# grbl_shield_hector.net
KiCad netlist of a schematic drawn in EAGLE
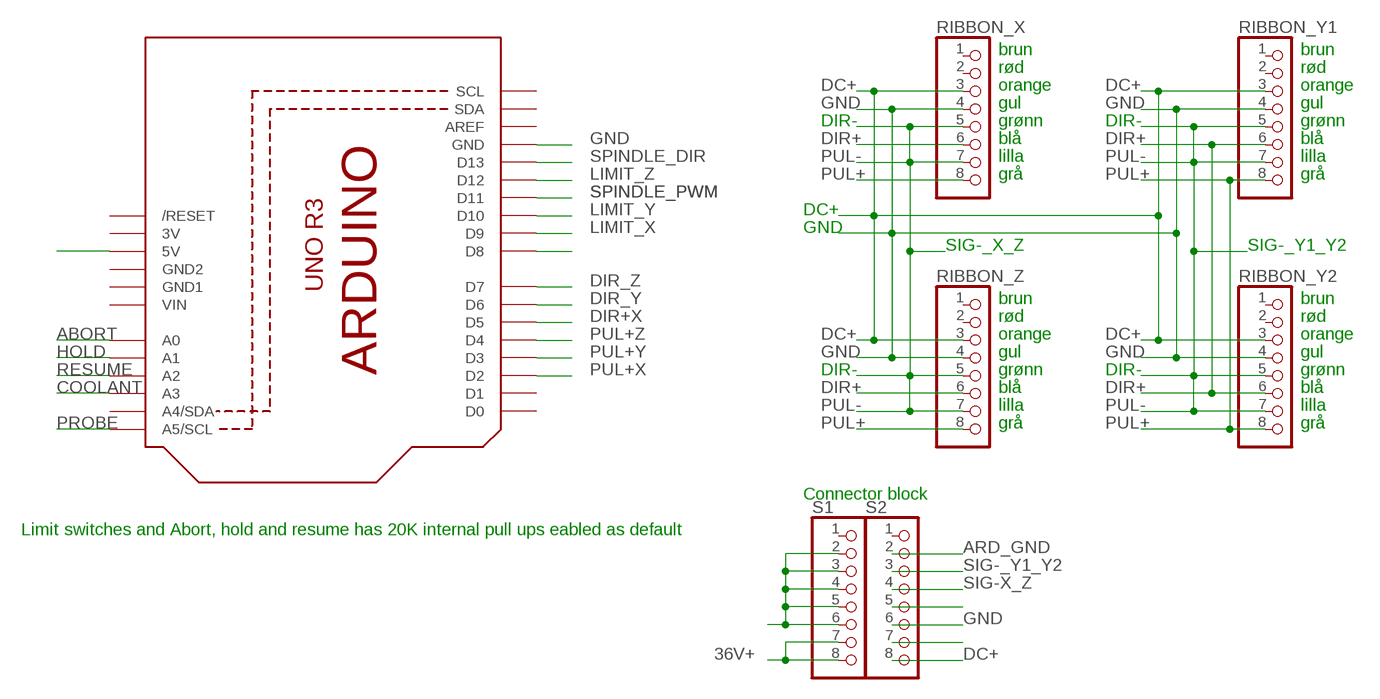
[diagram p0: schematic, sheet 1]

(export (version "E")
  (design (tool "Eeschema 10.0.6"))
  (components
    (comp (ref "Q1")
      (value "ARDUINOR3-NOIOREF-NOTEXT")
      (footprint "eagle-import:ARDUINOR3-NOTEXT-NOIOREF")
      (libsource (lib "eagle-import") (part "ARDUINOR3-NOIOREF-NOTEXT"))
    )
    (comp (ref "RIBBON_X")
      (value "PINHD-1X8")
      (footprint "eagle-import:1X08")
      (libsource (lib "eagle-import") (part "PINHD-1X8"))
    )
    (comp (ref "RIBBON_Y1")
      (value "PINHD-1X8")
      (footprint "eagle-import:1X08")
      (libsource (lib "eagle-import") (part "PINHD-1X8"))
    )
    (comp (ref "RIBBON_Y2")
      (value "PINHD-1X8")
      (footprint "eagle-import:1X08")
      (libsource (lib "eagle-import") (part "PINHD-1X8"))
    )
    (comp (ref "RIBBON_Z")
      (value "PINHD-1X8")
      (footprint "eagle-import:1X08")
      (libsource (lib "eagle-import") (part "PINHD-1X8"))
    )
    (comp (ref "S1")
      (value "PINHD-1X8")
      (footprint "eagle-import:1X08")
      (libsource (lib "eagle-import") (part "PINHD-1X8"))
    )
    (comp (ref "S2")
      (value "PINHD-1X8")
      (footprint "eagle-import:1X08")
      (libsource (lib "eagle-import") (part "PINHD-1X8"))
    )
  )
  (nets
    (net (code "1") (name "/3V") (class "Default")
      (node (ref "Q1") (pin "3V") (pinfunction "3V_3V") (pintype "power_in"))
    )
    (net (code "2") (name "/36V+") (class "Default")
      (node (ref "S1") (pin "7") (pinfunction "7_7") (pintype "passive"))
      (node (ref "S1") (pin "8") (pinfunction "8_8") (pintype "passive"))
    )
    (net (code "3") (name "/ABORT") (class "Default")
      (node (ref "Q1") (pin "A0") (pinfunction "A0_A0") (pintype "bidirectional"))
    )
    (net (code "4") (name "/ARD_GND") (class "Default")
      (node (ref "S2") (pin "2") (pinfunction "2_2") (pintype "passive"))
    )
    (net (code "5") (name "/COOLANT") (class "Default")
      (node (ref "Q1") (pin "A3") (pinfunction "A3_A3") (pintype "bidirectional"))
    )
    (net (code "6") (name "/DC+") (class "Default")
      (node (ref "RIBBON_X") (pin "3") (pinfunction "3_3") (pintype "passive"))
      (node (ref "RIBBON_Y1") (pin "3") (pinfunction "3_3") (pintype "passive"))
      (node (ref "RIBBON_Y2") (pin "3") (pinfunction "3_3") (pintype "passive"))
      (node (ref "RIBBON_Z") (pin "3") (pinfunction "3_3") (pintype "passive"))
      (node (ref "S2") (pin "8") (pinfunction "8_8") (pintype "passive"))
    )
    (net (code "7") (name "/DIR+") (class "Default")
      (node (ref "RIBBON_X") (pin "6") (pinfunction "6_6") (pintype "passive"))
      (node (ref "RIBBON_Y1") (pin "6") (pinfunction "6_6") (pintype "passive"))
      (node (ref "RIBBON_Y2") (pin "6") (pinfunction "6_6") (pintype "passive"))
      (node (ref "RIBBON_Z") (pin "6") (pinfunction "6_6") (pintype "passive"))
    )
    (net (code "8") (name "/DIR+X") (class "Default")
      (node (ref "Q1") (pin "D5") (pinfunction "D5_D5") (pintype "bidirectional"))
    )
    (net (code "9") (name "/DIR_Y") (class "Default")
      (node (ref "Q1") (pin "D6") (pinfunction "D6_D6") (pintype "bidirectional"))
    )
    (net (code "10") (name "/DIR_Z") (class "Default")
      (node (ref "Q1") (pin "D7") (pinfunction "D7_D7") (pintype "bidirectional"))
    )
    (net (code "11") (name "/GND") (class "Default")
      (node (ref "Q1") (pin "GND") (pinfunction "GND_GND") (pintype "power_in"))
      (node (ref "RIBBON_X") (pin "4") (pinfunction "4_4") (pintype "passive"))
      (node (ref "RIBBON_Y1") (pin "4") (pinfunction "4_4") (pintype "passive"))
      (node (ref "RIBBON_Y2") (pin "4") (pinfunction "4_4") (pintype "passive"))
      (node (ref "RIBBON_Z") (pin "4") (pinfunction "4_4") (pintype "passive"))
      (node (ref "S2") (pin "6") (pinfunction "6_6") (pintype "passive"))
    )
    (net (code "12") (name "/GND1") (class "Default")
      (node (ref "Q1") (pin "GND1") (pinfunction "GND1_GND1") (pintype "power_in"))
    )
    (net (code "13") (name "/GND2") (class "Default")
      (node (ref "Q1") (pin "GND2") (pinfunction "GND2_GND2") (pintype "power_in"))
    )
    (net (code "14") (name "/HOLD") (class "Default")
      (node (ref "Q1") (pin "A1") (pinfunction "A1_A1") (pintype "bidirectional"))
    )
    (net (code "15") (name "/LIMIT_X") (class "Default")
      (node (ref "Q1") (pin "D9") (pinfunction "D9_D9") (pintype "bidirectional"))
    )
    (net (code "16") (name "/LIMIT_Y") (class "Default")
      (node (ref "Q1") (pin "D10") (pinfunction "D10_D10") (pintype "bidirectional"))
    )
    (net (code "17") (name "/LIMIT_Z") (class "Default")
      (node (ref "Q1") (pin "D12") (pinfunction "D12_D12") (pintype "bidirectional"))
    )
    (net (code "18") (name "/PROBE") (class "Default")
      (node (ref "Q1") (pin "A5") (pinfunction "A5/SCL_A5") (pintype "bidirectional"))
    )
    (net (code "19") (name "/PUL+") (class "Default")
      (node (ref "RIBBON_X") (pin "8") (pinfunction "8_8") (pintype "passive"))
      (node (ref "RIBBON_Y1") (pin "8") (pinfunction "8_8") (pintype "passive"))
      (node (ref "RIBBON_Y2") (pin "8") (pinfunction "8_8") (pintype "passive"))
      (node (ref "RIBBON_Z") (pin "8") (pinfunction "8_8") (pintype "passive"))
    )
    (net (code "20") (name "/PUL+X") (class "Default")
      (node (ref "Q1") (pin "D2") (pinfunction "D2_D2") (pintype "bidirectional"))
    )
    (net (code "21") (name "/PUL+Y") (class "Default")
      (node (ref "Q1") (pin "D3") (pinfunction "D3_D3") (pintype "bidirectional"))
    )
    (net (code "22") (name "/PUL+Z") (class "Default")
      (node (ref "Q1") (pin "D4") (pinfunction "D4_D4") (pintype "bidirectional"))
    )
    (net (code "23") (name "/PUL-") (class "Default")
      (node (ref "RIBBON_X") (pin "5") (pinfunction "5_5") (pintype "passive"))
      (node (ref "RIBBON_X") (pin "7") (pinfunction "7_7") (pintype "passive"))
      (node (ref "RIBBON_Y1") (pin "5") (pinfunction "5_5") (pintype "passive"))
      (node (ref "RIBBON_Y1") (pin "7") (pinfunction "7_7") (pintype "passive"))
      (node (ref "RIBBON_Y2") (pin "5") (pinfunction "5_5") (pintype "passive"))
      (node (ref "RIBBON_Y2") (pin "7") (pinfunction "7_7") (pintype "passive"))
      (node (ref "RIBBON_Z") (pin "5") (pinfunction "5_5") (pintype "passive"))
      (node (ref "RIBBON_Z") (pin "7") (pinfunction "7_7") (pintype "passive"))
    )
    (net (code "24") (name "/RESUME") (class "Default")
      (node (ref "Q1") (pin "A2") (pinfunction "A2_A2") (pintype "bidirectional"))
    )
    (net (code "25") (name "/SIG-X_Z") (class "Default")
      (node (ref "S2") (pin "4") (pinfunction "4_4") (pintype "passive"))
    )
    (net (code "26") (name "/SIG-_Y1_Y2") (class "Default")
      (node (ref "S2") (pin "3") (pinfunction "3_3") (pintype "passive"))
    )
    (net (code "27") (name "/SPINDLE_DIR") (class "Default")
      (node (ref "Q1") (pin "D13") (pinfunction "D13_D13") (pintype "bidirectional"))
    )
    (net (code "28") (name "/SPINDLE_PWM") (class "Default")
      (node (ref "Q1") (pin "D11") (pinfunction "D11_D11") (pintype "bidirectional"))
    )
    (net (code "29") (name "/VIN") (class "Default")
      (node (ref "Q1") (pin "VIN") (pinfunction "VIN_VIN") (pintype "power_in"))
    )
    (net (code "30") (name "Net-(S1-Pad2)") (class "Default")
      (node (ref "S1") (pin "2") (pinfunction "2_2") (pintype "passive"))
      (node (ref "S1") (pin "3") (pinfunction "3_3") (pintype "passive"))
      (node (ref "S1") (pin "4") (pinfunction "4_4") (pintype "passive"))
      (node (ref "S1") (pin "5") (pinfunction "5_5") (pintype "passive"))
      (node (ref "S1") (pin "6") (pinfunction "6_6") (pintype "passive"))
    )
    (net (code "31") (name "unconnected-(Q1-A4{slash}SDA-PadA4)") (class "Default")
      (node (ref "Q1") (pin "A4") (pinfunction "A4/SDA_A4") (pintype "bidirectional"))
    )
    (net (code "32") (name "unconnected-(Q1-Pad5V)") (class "Default")
      (node (ref "Q1") (pin "5V") (pinfunction "5V_5V") (pintype "power_in"))
    )
    (net (code "33") (name "unconnected-(Q1-PadAREF)") (class "Default")
      (node (ref "Q1") (pin "AREF") (pinfunction "AREF_AREF") (pintype "bidirectional"))
    )
    (net (code "34") (name "unconnected-(Q1-PadD0)") (class "Default")
      (node (ref "Q1") (pin "D0") (pinfunction "D0_D0") (pintype "bidirectional"))
    )
    (net (code "35") (name "unconnected-(Q1-PadD1)") (class "Default")
      (node (ref "Q1") (pin "D1") (pinfunction "D1_D1") (pintype "bidirectional"))
    )
    (net (code "36") (name "unconnected-(Q1-PadD8)") (class "Default")
      (node (ref "Q1") (pin "D8") (pinfunction "D8_D8") (pintype "bidirectional"))
    )
    (net (code "37") (name "unconnected-(Q1-PadSCL)") (class "Default")
      (node (ref "Q1") (pin "SCL") (pinfunction "SCL_SCL") (pintype "bidirectional"))
    )
    (net (code "38") (name "unconnected-(Q1-PadSDA)") (class "Default")
      (node (ref "Q1") (pin "SDA") (pinfunction "SDA_SDA") (pintype "bidirectional"))
    )
    (net (code "39") (name "unconnected-(Q1-{slash}RESET-PadRESET)") (class "Default")
      (node (ref "Q1") (pin "RESET") (pinfunction "/RESET_RESET") (pintype "bidirectional"))
    )
    (net (code "40") (name "unconnected-(RIBBON_X-Pad1)") (class "Default")
      (node (ref "RIBBON_X") (pin "1") (pinfunction "1_1") (pintype "passive"))
    )
    (net (code "41") (name "unconnected-(RIBBON_X-Pad2)") (class "Default")
      (node (ref "RIBBON_X") (pin "2") (pinfunction "2_2") (pintype "passive"))
    )
    (net (code "42") (name "unconnected-(RIBBON_Y1-Pad1)") (class "Default")
      (node (ref "RIBBON_Y1") (pin "1") (pinfunction "1_1") (pintype "passive"))
    )
    (net (code "43") (name "unconnected-(RIBBON_Y1-Pad2)") (class "Default")
      (node (ref "RIBBON_Y1") (pin "2") (pinfunction "2_2") (pintype "passive"))
    )
    (net (code "44") (name "unconnected-(RIBBON_Y2-Pad1)") (class "Default")
      (node (ref "RIBBON_Y2") (pin "1") (pinfunction "1_1") (pintype "passive"))
    )
    (net (code "45") (name "unconnected-(RIBBON_Y2-Pad2)") (class "Default")
      (node (ref "RIBBON_Y2") (pin "2") (pinfunction "2_2") (pintype "passive"))
    )
    (net (code "46") (name "unconnected-(RIBBON_Z-Pad1)") (class "Default")
      (node (ref "RIBBON_Z") (pin "1") (pinfunction "1_1") (pintype "passive"))
    )
    (net (code "47") (name "unconnected-(RIBBON_Z-Pad2)") (class "Default")
      (node (ref "RIBBON_Z") (pin "2") (pinfunction "2_2") (pintype "passive"))
    )
    (net (code "48") (name "unconnected-(S1-Pad1)") (class "Default")
      (node (ref "S1") (pin "1") (pinfunction "1_1") (pintype "passive"))
    )
    (net (code "49") (name "unconnected-(S2-Pad1)") (class "Default")
      (node (ref "S2") (pin "1") (pinfunction "1_1") (pintype "passive"))
    )
    (net (code "50") (name "unconnected-(S2-Pad5)") (class "Default")
      (node (ref "S2") (pin "5") (pinfunction "5_5") (pintype "passive"))
    )
    (net (code "51") (name "unconnected-(S2-Pad7)") (class "Default")
      (node (ref "S2") (pin "7") (pinfunction "7_7") (pintype "passive"))
    )
  )
)
